# 5_Keys.net
KiCad netlist of a schematic drawn in Altium Designer
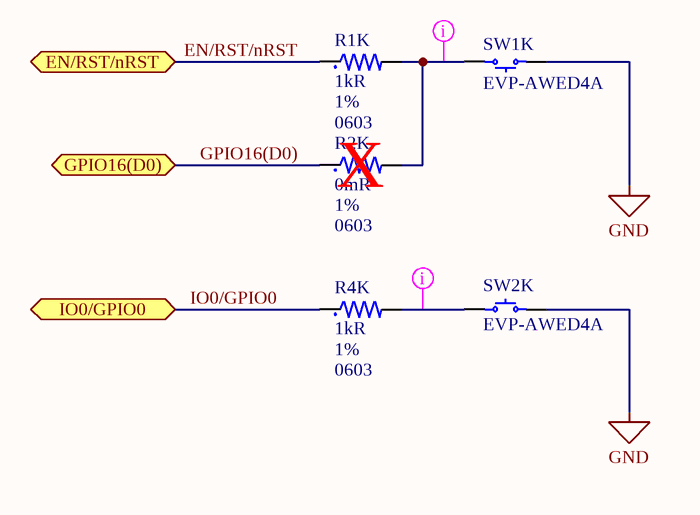
[diagram p0: 5_Keys.SchDoc]

(export (version "E")
  (design (tool "Eeschema 10.0.6"))
  (components
    (comp (ref "R1K")
      (value "1kR")
      (footprint "R0603-MFG")
      (description "SMD Chip Resistor, 1 kOhm, ± 1%, 100 mW, 0603 [1608 Metric], Thick Film, General Purpose")
      (fields
        (field (name "MANUFACTURER") "Yageo")
        (field (name "MANUFACTURER PART NUMBER") "RC0603FR-101KL")
        (field (name "TOLERANCE") "1%")
        (field (name "CASE/PACKAGE") "0603")
      )
      (libsource (lib "Lib_Register_0603") (part "1K"))
    )
    (comp (ref "R2K")
      (value "0mR")
      (footprint "R0603-MFG")
      (description "Zero Ohm Resistor, Jumper, 0603 [1608 Metric], Thick Film, 100 mW, 1 A, Surface Mount")
      (fields
        (field (name "MANUFACTURER") "Yageo")
        (field (name "MANUFACTURER PART NUMBER") "RC0603JR-070RL")
        (field (name "TOLERANCE") "1%")
        (field (name "CASE/PACKAGE") "0603")
      )
      (libsource (lib "Lib_Register_0603") (part "0R"))
    )
    (comp (ref "R4K")
      (value "1kR")
      (footprint "R0603-MFG")
      (description "SMD Chip Resistor, 1 kOhm, ± 1%, 100 mW, 0603 [1608 Metric], Thick Film, General Purpose")
      (fields
        (field (name "MANUFACTURER") "Yageo")
        (field (name "MANUFACTURER PART NUMBER") "RC0603FR-101KL")
        (field (name "TOLERANCE") "1%")
        (field (name "CASE/PACKAGE") "0603")
      )
      (libsource (lib "Lib_Register_0603") (part "1K"))
    )
    (comp (ref "SW1K")
      (value "EVP-AWED4A")
      (footprint "PANASONIC EVPAW")
      (description "3.0MM X 2.0MM / 3.3N / 0.15MM ST")
      (fields (field (name "MANUFACTURER") "Panasonic Electronic Components"))
      (libsource (lib "Celestial Altium Library - altium_library") (part "SPST-NO 2 PIN"))
    )
    (comp (ref "SW2K")
      (value "EVP-AWED4A")
      (footprint "PANASONIC EVPAW")
      (description "3.0MM X 2.0MM / 3.3N / 0.15MM ST")
      (fields (field (name "MANUFACTURER") "Panasonic Electronic Components"))
      (libsource (lib "Celestial Altium Library - altium_library") (part "SPST-NO 2 PIN"))
    )
  )
  (nets
    (net (code "1") (name "/EN{slash}RST{slash}nRST") (class "Default")
      (node (ref "R1K") (pin "1") (pinfunction "1_1") (pintype "passive"))
    )
    (net (code "2") (name "/GPIO16(D0)") (class "Default")
      (node (ref "R2K") (pin "1") (pinfunction "1_1") (pintype "passive"))
    )
    (net (code "3") (name "/IO0{slash}GPIO0") (class "Default")
      (node (ref "R4K") (pin "1") (pinfunction "1_1") (pintype "passive"))
    )
    (net (code "4") (name "GND") (class "Default")
      (node (ref "SW1K") (pin "1") (pinfunction "1_1") (pintype "passive"))
      (node (ref "SW2K") (pin "2") (pinfunction "2_2") (pintype "passive"))
    )
    (net (code "5") (name "Net-(R1K-Pad2)") (class "Default")
      (node (ref "R1K") (pin "2") (pinfunction "2_2") (pintype "passive"))
      (node (ref "R2K") (pin "2") (pinfunction "2_2") (pintype "passive"))
      (node (ref "SW1K") (pin "2") (pinfunction "2_2") (pintype "passive"))
    )
    (net (code "6") (name "Net-(R4K-Pad2)") (class "Default")
      (node (ref "R4K") (pin "2") (pinfunction "2_2") (pintype "passive"))
      (node (ref "SW2K") (pin "1") (pinfunction "1_1") (pintype "passive"))
    )
  )
)
